# TRV_RFM23_V0_1.net
KiCad netlist of a schematic drawn in EAGLE
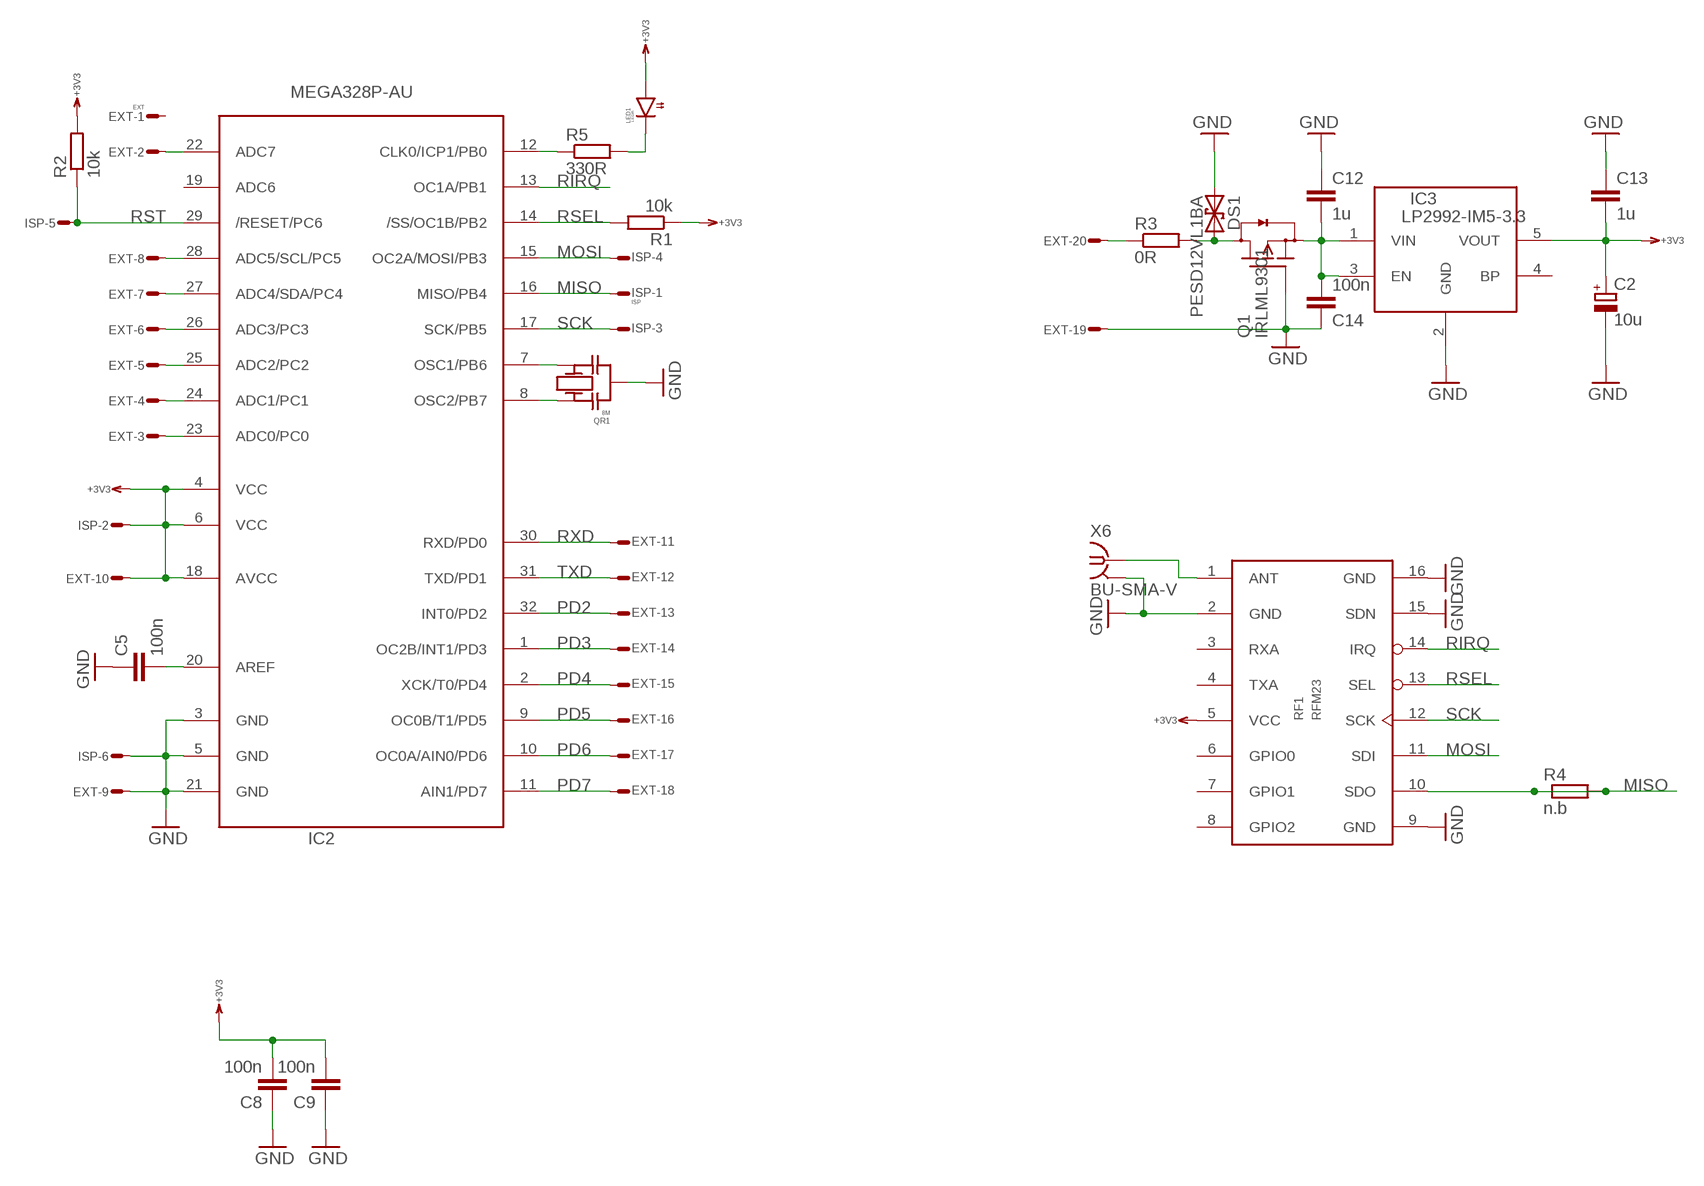
[diagram p0: schematic, sheet 1]

(export (version "E")
  (design (tool "Eeschema 10.0.6"))
  (components
    (comp (ref "C2")
      (value "10u")
      (footprint "eagle-import:SMC_B")
      (libsource (lib "eagle-import") (part "C_POLSMCB"))
    )
    (comp (ref "C5")
      (value "100n")
      (footprint "eagle-import:0603")
      (libsource (lib "eagle-import") (part "C0603"))
    )
    (comp (ref "C8")
      (value "100n")
      (footprint "eagle-import:0603")
      (libsource (lib "eagle-import") (part "C0603"))
    )
    (comp (ref "C9")
      (value "100n")
      (footprint "eagle-import:0603")
      (libsource (lib "eagle-import") (part "C0603"))
    )
    (comp (ref "C12")
      (value "1u")
      (footprint "eagle-import:0603")
      (libsource (lib "eagle-import") (part "C0603"))
    )
    (comp (ref "C13")
      (value "1u")
      (footprint "eagle-import:0603")
      (libsource (lib "eagle-import") (part "C0603"))
    )
    (comp (ref "C14")
      (value "100n")
      (footprint "eagle-import:0603")
      (libsource (lib "eagle-import") (part "C0603"))
    )
    (comp (ref "DS1")
      (value "PESD12VL1BA")
      (footprint "eagle-import:SOD323")
      (libsource (lib "eagle-import") (part "TVS-U323"))
    )
    (comp (ref "EXT")
      (value "EXT")
      (footprint "eagle-import:ML20S")
      (libsource (lib "eagle-import") (part "ML20?ES"))
    )
    (comp (ref "IC2")
      (value "MEGA328P-AU")
      (footprint "eagle-import:TQFP32-08")
      (libsource (lib "eagle-import") (part "MEGA168PA"))
    )
    (comp (ref "IC3")
      (value "LP2992-IM5-3.3")
      (footprint "eagle-import:SOT23-5")
      (libsource (lib "eagle-import") (part "LDO"))
    )
    (comp (ref "ISP")
      (value "ISP")
      (footprint "eagle-import:ML6S")
      (libsource (lib "eagle-import") (part "ML6ES"))
    )
    (comp (ref "LED1")
      (value "LEDR")
      (footprint "eagle-import:0805")
      (libsource (lib "eagle-import") (part "LED0805"))
    )
    (comp (ref "Q1")
      (value "IRLML9301")
      (footprint "eagle-import:SOT23")
      (libsource (lib "eagle-import") (part "FET-PDSOT23"))
    )
    (comp (ref "QR1")
      (value "8M")
      (footprint "eagle-import:CR")
      (libsource (lib "eagle-import") (part "QRCR"))
    )
    (comp (ref "R1")
      (value "10k")
      (footprint "eagle-import:0603")
      (libsource (lib "eagle-import") (part "R0603"))
    )
    (comp (ref "R2")
      (value "10k")
      (footprint "eagle-import:0603")
      (libsource (lib "eagle-import") (part "R0603"))
    )
    (comp (ref "R3")
      (value "0R")
      (footprint "eagle-import:0603")
      (libsource (lib "eagle-import") (part "R0603"))
    )
    (comp (ref "R4")
      (value "n.b")
      (footprint "eagle-import:0603")
      (libsource (lib "eagle-import") (part "R0603"))
    )
    (comp (ref "R5")
      (value "330R")
      (footprint "eagle-import:0603")
      (libsource (lib "eagle-import") (part "R0603"))
    )
    (comp (ref "RF1")
      (value "RFM23")
      (footprint "eagle-import:RFM23B")
      (libsource (lib "eagle-import") (part "RFM22S1"))
    )
    (comp (ref "X6")
      (value "BU-SMA-V")
      (footprint "eagle-import:BU-SMA-V")
      (libsource (lib "eagle-import") (part "BU-SMA-V"))
    )
  )
  (nets
    (net (code "1") (name "+3V3") (class "Default")
      (node (ref "C13") (pin "2") (pinfunction "2_2") (pintype "passive"))
      (node (ref "C2") (pin "+") (pinfunction "+_+") (pintype "passive"))
      (node (ref "C8") (pin "2") (pinfunction "2_2") (pintype "passive"))
      (node (ref "C9") (pin "2") (pinfunction "2_2") (pintype "passive"))
      (node (ref "EXT") (pin "10") (pinfunction "S_10") (pintype "passive"))
      (node (ref "IC2") (pin "18") (pinfunction "AVCC_18") (pintype "bidirectional"))
      (node (ref "IC2") (pin "4") (pinfunction "VCC_4") (pintype "bidirectional"))
      (node (ref "IC2") (pin "6") (pinfunction "VCC_6") (pintype "bidirectional"))
      (node (ref "IC3") (pin "5") (pinfunction "VOUT_5") (pintype "bidirectional"))
      (node (ref "ISP") (pin "2") (pinfunction "S_2") (pintype "passive"))
      (node (ref "LED1") (pin "C") (pinfunction "A_C") (pintype "bidirectional"))
      (node (ref "R1") (pin "1") (pinfunction "1_1") (pintype "passive"))
      (node (ref "R2") (pin "2") (pinfunction "2_2") (pintype "passive"))
      (node (ref "RF1") (pin "5") (pinfunction "VCC_5") (pintype "input"))
    )
    (net (code "2") (name "/MISO") (class "Default")
      (node (ref "IC2") (pin "16") (pinfunction "MISO/PB4_16") (pintype "bidirectional"))
      (node (ref "ISP") (pin "1") (pinfunction "S_1") (pintype "passive"))
      (node (ref "R4") (pin "1") (pinfunction "1_1") (pintype "passive"))
      (node (ref "R4") (pin "2") (pinfunction "2_2") (pintype "passive"))
      (node (ref "RF1") (pin "10") (pinfunction "SDO_10") (pintype "output"))
    )
    (net (code "3") (name "/MOSI") (class "Default")
      (node (ref "IC2") (pin "15") (pinfunction "OC2A/MOSI/PB3_15") (pintype "bidirectional"))
      (node (ref "ISP") (pin "4") (pinfunction "S_4") (pintype "passive"))
      (node (ref "RF1") (pin "11") (pinfunction "SDI_11") (pintype "input"))
    )
    (net (code "4") (name "/PD2") (class "Default")
      (node (ref "EXT") (pin "13") (pinfunction "S_13") (pintype "passive"))
      (node (ref "IC2") (pin "32") (pinfunction "INT0/PD2_32") (pintype "bidirectional"))
    )
    (net (code "5") (name "/PD3") (class "Default")
      (node (ref "EXT") (pin "14") (pinfunction "S_14") (pintype "passive"))
      (node (ref "IC2") (pin "1") (pinfunction "OC2B/INT1/PD3_1") (pintype "bidirectional"))
    )
    (net (code "6") (name "/PD4") (class "Default")
      (node (ref "EXT") (pin "15") (pinfunction "S_15") (pintype "passive"))
      (node (ref "IC2") (pin "2") (pinfunction "XCK/T0/PD4_2") (pintype "bidirectional"))
    )
    (net (code "7") (name "/PD5") (class "Default")
      (node (ref "EXT") (pin "16") (pinfunction "S_16") (pintype "passive"))
      (node (ref "IC2") (pin "9") (pinfunction "OC0B/T1/PD5_9") (pintype "bidirectional"))
    )
    (net (code "8") (name "/PD6") (class "Default")
      (node (ref "EXT") (pin "17") (pinfunction "S_17") (pintype "passive"))
      (node (ref "IC2") (pin "10") (pinfunction "OC0A/AIN0/PD6_10") (pintype "bidirectional"))
    )
    (net (code "9") (name "/PD7") (class "Default")
      (node (ref "EXT") (pin "18") (pinfunction "S_18") (pintype "passive"))
      (node (ref "IC2") (pin "11") (pinfunction "AIN1/PD7_11") (pintype "bidirectional"))
    )
    (net (code "10") (name "/RIRQ") (class "Default")
      (node (ref "IC2") (pin "13") (pinfunction "OC1A/PB1_13") (pintype "bidirectional"))
      (node (ref "RF1") (pin "14") (pinfunction "IRQ_14") (pintype "open_collector"))
    )
    (net (code "11") (name "/RSEL") (class "Default")
      (node (ref "IC2") (pin "14") (pinfunction "/SS/OC1B/PB2_14") (pintype "bidirectional"))
      (node (ref "R1") (pin "2") (pinfunction "2_2") (pintype "passive"))
      (node (ref "RF1") (pin "13") (pinfunction "SEL_13") (pintype "input"))
    )
    (net (code "12") (name "/RST") (class "Default")
      (node (ref "IC2") (pin "29") (pinfunction "/RESET/PC6_29") (pintype "bidirectional"))
      (node (ref "ISP") (pin "5") (pinfunction "S_5") (pintype "passive"))
      (node (ref "R2") (pin "1") (pinfunction "1_1") (pintype "passive"))
    )
    (net (code "13") (name "/RXD") (class "Default")
      (node (ref "EXT") (pin "11") (pinfunction "S_11") (pintype "passive"))
      (node (ref "IC2") (pin "30") (pinfunction "RXD/PD0_30") (pintype "bidirectional"))
    )
    (net (code "14") (name "/SCK") (class "Default")
      (node (ref "IC2") (pin "17") (pinfunction "SCK/PB5_17") (pintype "bidirectional"))
      (node (ref "ISP") (pin "3") (pinfunction "S_3") (pintype "passive"))
      (node (ref "RF1") (pin "12") (pinfunction "SCK_12") (pintype "input"))
    )
    (net (code "15") (name "/TXD") (class "Default")
      (node (ref "EXT") (pin "12") (pinfunction "S_12") (pintype "passive"))
      (node (ref "IC2") (pin "31") (pinfunction "TXD/PD1_31") (pintype "bidirectional"))
    )
    (net (code "16") (name "GND") (class "Default")
      (node (ref "C12") (pin "1") (pinfunction "1_1") (pintype "passive"))
      (node (ref "C13") (pin "1") (pinfunction "1_1") (pintype "passive"))
      (node (ref "C14") (pin "1") (pinfunction "1_1") (pintype "passive"))
      (node (ref "C2") (pin "-") (pinfunction "-_-") (pintype "passive"))
      (node (ref "C5") (pin "1") (pinfunction "1_1") (pintype "passive"))
      (node (ref "C8") (pin "1") (pinfunction "1_1") (pintype "passive"))
      (node (ref "C9") (pin "1") (pinfunction "1_1") (pintype "passive"))
      (node (ref "DS1") (pin "A") (pinfunction "1_A") (pintype "passive"))
      (node (ref "EXT") (pin "19") (pinfunction "S_19") (pintype "passive"))
      (node (ref "EXT") (pin "9") (pinfunction "S_9") (pintype "passive"))
      (node (ref "IC2") (pin "21") (pinfunction "GND_21") (pintype "bidirectional"))
      (node (ref "IC2") (pin "3") (pinfunction "GND_3") (pintype "bidirectional"))
      (node (ref "IC2") (pin "5") (pinfunction "GND_5") (pintype "bidirectional"))
      (node (ref "IC3") (pin "2") (pinfunction "GND_2") (pintype "bidirectional"))
      (node (ref "ISP") (pin "6") (pinfunction "S_6") (pintype "passive"))
      (node (ref "Q1") (pin "1") (pinfunction "G_1") (pintype "passive"))
      (node (ref "QR1") (pin "M") (pinfunction "M_M") (pintype "passive"))
      (node (ref "RF1") (pin "15") (pinfunction "SDN_15") (pintype "input"))
      (node (ref "RF1") (pin "16") (pinfunction "GND_16") (pintype "input"))
      (node (ref "RF1") (pin "2") (pinfunction "GND_2") (pintype "input"))
      (node (ref "RF1") (pin "9") (pinfunction "GND_9") (pintype "input"))
      (node (ref "X6") (pin "2") (pinfunction "GND_2") (pintype "power_in"))
    )
    (net (code "17") (name "Net-(DS1-2)") (class "Default")
      (node (ref "DS1") (pin "C") (pinfunction "2_C") (pintype "passive"))
      (node (ref "Q1") (pin "3") (pinfunction "D_3") (pintype "passive"))
      (node (ref "R3") (pin "2") (pinfunction "2_2") (pintype "passive"))
    )
    (net (code "18") (name "Net-(EXTL-S)") (class "Default")
      (node (ref "EXT") (pin "2") (pinfunction "S_2") (pintype "passive"))
      (node (ref "IC2") (pin "22") (pinfunction "ADC7_22") (pintype "bidirectional"))
    )
    (net (code "19") (name "Net-(EXTM-S)") (class "Default")
      (node (ref "EXT") (pin "20") (pinfunction "S_20") (pintype "passive"))
      (node (ref "R3") (pin "1") (pinfunction "1_1") (pintype "passive"))
    )
    (net (code "20") (name "Net-(EXTN-S)") (class "Default")
      (node (ref "EXT") (pin "3") (pinfunction "S_3") (pintype "passive"))
      (node (ref "IC2") (pin "23") (pinfunction "ADC0/PC0_23") (pintype "bidirectional"))
    )
    (net (code "21") (name "Net-(EXTO-S)") (class "Default")
      (node (ref "EXT") (pin "4") (pinfunction "S_4") (pintype "passive"))
      (node (ref "IC2") (pin "24") (pinfunction "ADC1/PC1_24") (pintype "bidirectional"))
    )
    (net (code "22") (name "Net-(EXTP-S)") (class "Default")
      (node (ref "EXT") (pin "5") (pinfunction "S_5") (pintype "passive"))
      (node (ref "IC2") (pin "25") (pinfunction "ADC2/PC2_25") (pintype "bidirectional"))
    )
    (net (code "23") (name "Net-(EXTQ-S)") (class "Default")
      (node (ref "EXT") (pin "6") (pinfunction "S_6") (pintype "passive"))
      (node (ref "IC2") (pin "26") (pinfunction "ADC3/PC3_26") (pintype "bidirectional"))
    )
    (net (code "24") (name "Net-(EXTR-S)") (class "Default")
      (node (ref "EXT") (pin "7") (pinfunction "S_7") (pintype "passive"))
      (node (ref "IC2") (pin "27") (pinfunction "ADC4/SDA/PC4_27") (pintype "bidirectional"))
    )
    (net (code "25") (name "Net-(EXTS-S)") (class "Default")
      (node (ref "EXT") (pin "8") (pinfunction "S_8") (pintype "passive"))
      (node (ref "IC2") (pin "28") (pinfunction "ADC5/SCL/PC5_28") (pintype "bidirectional"))
    )
    (net (code "26") (name "Net-(IC2-AREF)") (class "Default")
      (node (ref "C5") (pin "2") (pinfunction "2_2") (pintype "passive"))
      (node (ref "IC2") (pin "20") (pinfunction "AREF_20") (pintype "bidirectional"))
    )
    (net (code "27") (name "Net-(IC2-CLK0{slash}ICP1{slash}PB0)") (class "Default")
      (node (ref "IC2") (pin "12") (pinfunction "CLK0/ICP1/PB0_12") (pintype "bidirectional"))
      (node (ref "R5") (pin "1") (pinfunction "1_1") (pintype "passive"))
    )
    (net (code "28") (name "Net-(IC2-OSC1{slash}PB6)") (class "Default")
      (node (ref "IC2") (pin "7") (pinfunction "OSC1/PB6_7") (pintype "bidirectional"))
      (node (ref "QR1") (pin "2") (pinfunction "2_2") (pintype "passive"))
    )
    (net (code "29") (name "Net-(IC2-OSC2{slash}PB7)") (class "Default")
      (node (ref "IC2") (pin "8") (pinfunction "OSC2/PB7_8") (pintype "bidirectional"))
      (node (ref "QR1") (pin "1") (pinfunction "1_1") (pintype "passive"))
    )
    (net (code "30") (name "Net-(IC3-EN)") (class "Default")
      (node (ref "C12") (pin "2") (pinfunction "2_2") (pintype "passive"))
      (node (ref "C14") (pin "2") (pinfunction "2_2") (pintype "passive"))
      (node (ref "IC3") (pin "1") (pinfunction "VIN_1") (pintype "bidirectional"))
      (node (ref "IC3") (pin "3") (pinfunction "EN_3") (pintype "bidirectional"))
      (node (ref "Q1") (pin "2") (pinfunction "S_2") (pintype "passive"))
    )
    (net (code "31") (name "Net-(LED1-C)") (class "Default")
      (node (ref "LED1") (pin "A") (pinfunction "C_A") (pintype "bidirectional"))
      (node (ref "R5") (pin "2") (pinfunction "2_2") (pintype "passive"))
    )
    (net (code "32") (name "Net-(RF1-ANT)") (class "Default")
      (node (ref "RF1") (pin "1") (pinfunction "ANT_1") (pintype "output"))
      (node (ref "X6") (pin "1") (pinfunction "1_1") (pintype "passive"))
    )
    (net (code "33") (name "unconnected-(EXTA-S-Pad1)") (class "Default")
      (node (ref "EXT") (pin "1") (pinfunction "S_1") (pintype "passive"))
    )
    (net (code "34") (name "unconnected-(IC2-ADC6-Pad19)") (class "Default")
      (node (ref "IC2") (pin "19") (pinfunction "ADC6_19") (pintype "bidirectional"))
    )
    (net (code "35") (name "unconnected-(IC3-BP-Pad4)") (class "Default")
      (node (ref "IC3") (pin "4") (pinfunction "BP_4") (pintype "bidirectional"))
    )
    (net (code "36") (name "unconnected-(RF1-GPIO0-Pad6)") (class "Default")
      (node (ref "RF1") (pin "6") (pinfunction "GPIO0_6") (pintype "bidirectional"))
    )
    (net (code "37") (name "unconnected-(RF1-GPIO1-Pad7)") (class "Default")
      (node (ref "RF1") (pin "7") (pinfunction "GPIO1_7") (pintype "bidirectional"))
    )
    (net (code "38") (name "unconnected-(RF1-GPIO2-Pad8)") (class "Default")
      (node (ref "RF1") (pin "8") (pinfunction "GPIO2_8") (pintype "bidirectional"))
    )
    (net (code "39") (name "unconnected-(RF1-RXA-Pad3)") (class "Default")
      (node (ref "RF1") (pin "3") (pinfunction "RXA_3") (pintype "input"))
    )
    (net (code "40") (name "unconnected-(RF1-TXA-Pad4)") (class "Default")
      (node (ref "RF1") (pin "4") (pinfunction "TXA_4") (pintype "input"))
    )
  )
)
